# LED_SEQUENCER.net
KiCad netlist of a schematic drawn in Altium Designer
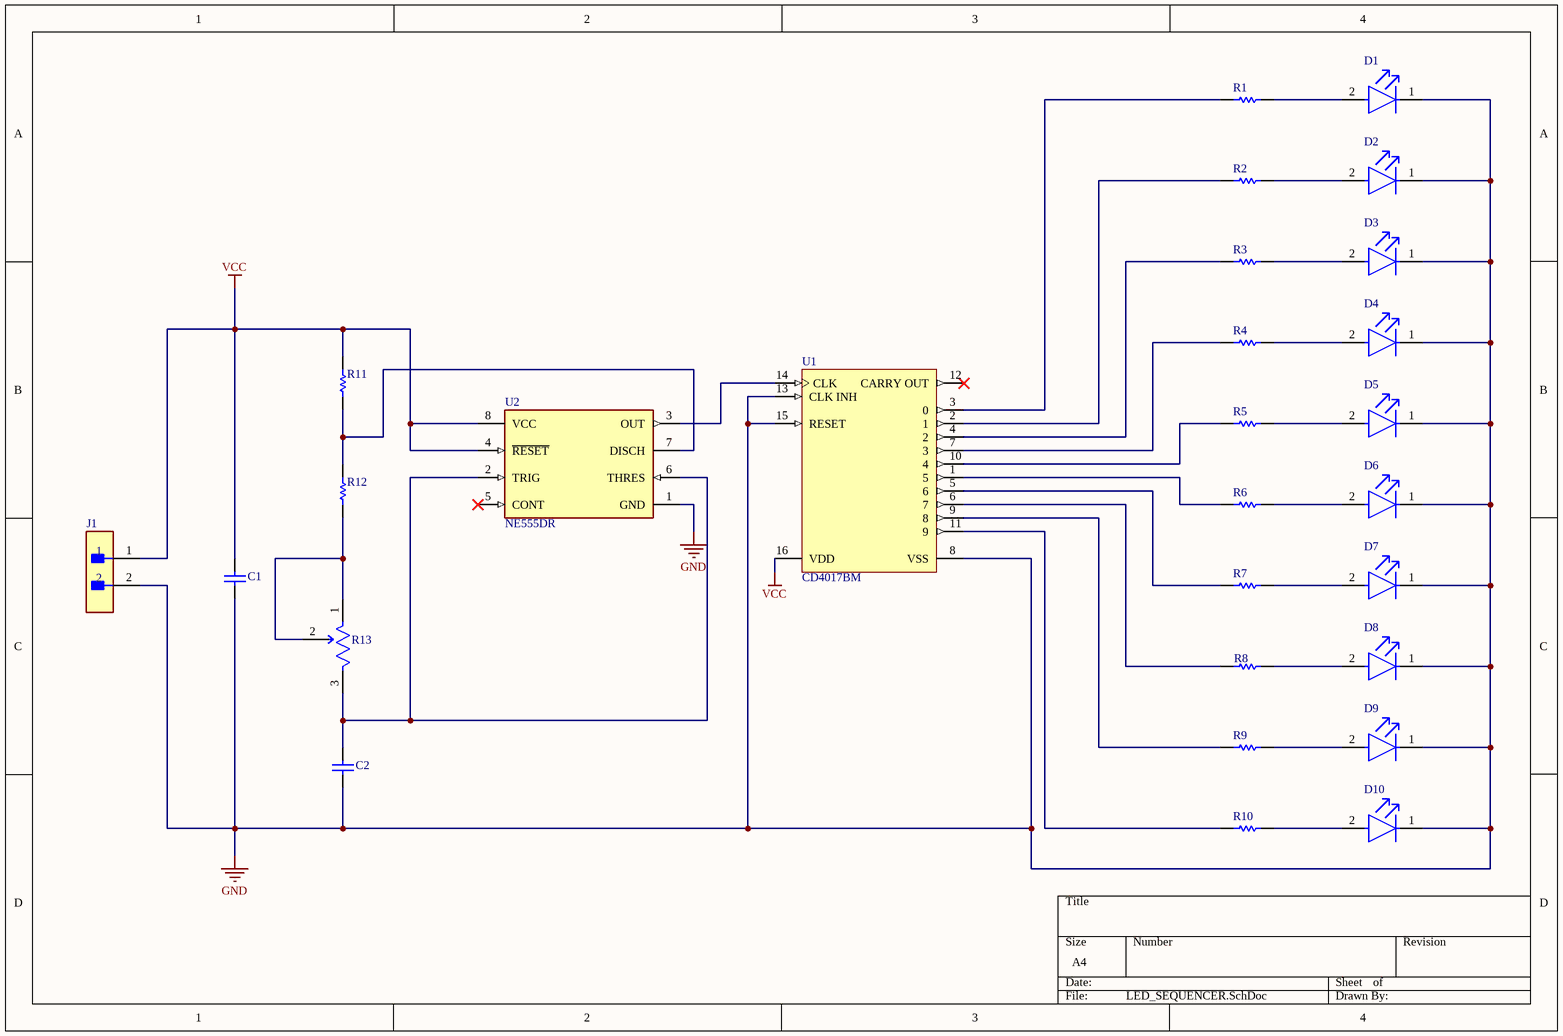
[diagram p0: LED_SEQUENCER.SchDoc]

(export (version "E")
  (design (tool "Eeschema 10.0.6"))
  (components
    (comp (ref "C1")
      (value "GRM21BR71H105KA12L")
      (footprint "CAPC2013X135X45LL10T25")
      (fields (field (name "MANUFACTURER") "Murata"))
      (libsource (lib "Altium Content Vault") (part "CAP"))
    )
    (comp (ref "C2")
      (value "GRM21BR71H105KA12L")
      (footprint "CAPC2013X135X45LL10T25")
      (fields (field (name "MANUFACTURER") "Murata"))
      (libsource (lib "Altium Content Vault") (part "CAP"))
    )
    (comp (ref "D1")
      (value "HLMP-1301")
      (footprint "FP-HLMP-1301-MFG")
      (description "LED RED DIFFUSED T-1 T/H")
      (fields
        (field (name "OCTOPART") "https://octopart.com/hlmp-1301-broadcom-71130345")
        (field (name "MANUFACTURER") "Broadcom")
      )
      (libsource (lib "Altium Content Vault") (part "8706943c75ba83719d021d2fdc84c58"))
    )
    (comp (ref "D2")
      (value "HLMP-1301")
      (footprint "FP-HLMP-1301-MFG")
      (description "LED RED DIFFUSED T-1 T/H")
      (fields
        (field (name "OCTOPART") "https://octopart.com/hlmp-1301-broadcom-71130345")
        (field (name "MANUFACTURER") "Broadcom")
      )
      (libsource (lib "Altium Content Vault") (part "8706943c75ba83719d021d2fdc84c58"))
    )
    (comp (ref "D3")
      (value "HLMP-1301")
      (footprint "FP-HLMP-1301-MFG")
      (description "LED RED DIFFUSED T-1 T/H")
      (fields
        (field (name "OCTOPART") "https://octopart.com/hlmp-1301-broadcom-71130345")
        (field (name "MANUFACTURER") "Broadcom")
      )
      (libsource (lib "Altium Content Vault") (part "8706943c75ba83719d021d2fdc84c58"))
    )
    (comp (ref "D4")
      (value "HLMP-1301")
      (footprint "FP-HLMP-1301-MFG")
      (description "LED RED DIFFUSED T-1 T/H")
      (fields
        (field (name "OCTOPART") "https://octopart.com/hlmp-1301-broadcom-71130345")
        (field (name "MANUFACTURER") "Broadcom")
      )
      (libsource (lib "Altium Content Vault") (part "8706943c75ba83719d021d2fdc84c58"))
    )
    (comp (ref "D5")
      (value "HLMP-1301")
      (footprint "FP-HLMP-1301-MFG")
      (description "LED RED DIFFUSED T-1 T/H")
      (fields
        (field (name "OCTOPART") "https://octopart.com/hlmp-1301-broadcom-71130345")
        (field (name "MANUFACTURER") "Broadcom")
      )
      (libsource (lib "Altium Content Vault") (part "8706943c75ba83719d021d2fdc84c58"))
    )
    (comp (ref "D6")
      (value "HLMP-1301")
      (footprint "FP-HLMP-1301-MFG")
      (description "LED RED DIFFUSED T-1 T/H")
      (fields
        (field (name "OCTOPART") "https://octopart.com/hlmp-1301-broadcom-71130345")
        (field (name "MANUFACTURER") "Broadcom")
      )
      (libsource (lib "Altium Content Vault") (part "8706943c75ba83719d021d2fdc84c58"))
    )
    (comp (ref "D7")
      (value "HLMP-1301")
      (footprint "FP-HLMP-1301-MFG")
      (description "LED RED DIFFUSED T-1 T/H")
      (fields
        (field (name "OCTOPART") "https://octopart.com/hlmp-1301-broadcom-71130345")
        (field (name "MANUFACTURER") "Broadcom")
      )
      (libsource (lib "Altium Content Vault") (part "8706943c75ba83719d021d2fdc84c58"))
    )
    (comp (ref "D8")
      (value "HLMP-1301")
      (footprint "FP-HLMP-1301-MFG")
      (description "LED RED DIFFUSED T-1 T/H")
      (fields
        (field (name "OCTOPART") "https://octopart.com/hlmp-1301-broadcom-71130345")
        (field (name "MANUFACTURER") "Broadcom")
      )
      (libsource (lib "Altium Content Vault") (part "8706943c75ba83719d021d2fdc84c58"))
    )
    (comp (ref "D9")
      (value "HLMP-1301")
      (footprint "FP-HLMP-1301-MFG")
      (description "LED RED DIFFUSED T-1 T/H")
      (fields
        (field (name "OCTOPART") "https://octopart.com/hlmp-1301-broadcom-71130345")
        (field (name "MANUFACTURER") "Broadcom")
      )
      (libsource (lib "Altium Content Vault") (part "8706943c75ba83719d021d2fdc84c58"))
    )
    (comp (ref "D10")
      (value "HLMP-1301")
      (footprint "FP-HLMP-1301-MFG")
      (description "LED RED DIFFUSED T-1 T/H")
      (fields
        (field (name "OCTOPART") "https://octopart.com/hlmp-1301-broadcom-71130345")
        (field (name "MANUFACTURER") "Broadcom")
      )
      (libsource (lib "Altium Content Vault") (part "8706943c75ba83719d021d2fdc84c58"))
    )
    (comp (ref "J1")
      (value "M20-9990246")
      (footprint "FP-M20-9990246-MFG")
      (description "Connector Header Through Hole 2 position 0.100\" (2.54mm)")
      (fields (field (name "OCTOPART") "https://octopart.com/m20-9990246-harwin-2590635"))
      (libsource (lib "Altium Content Vault") (part "3bc925449376181038e59eaffc5286c"))
    )
    (comp (ref "R1")
      (value "RC0805FR-071KL")
      (footprint "RESC2013X60X35ML10T20")
      (description "Chip Resistor, 1 KOhm, +/- 1%, 125 mW, -55 to 155 degC, 0805 (2012 Metric), RoHS, Tape and Reel")
      (fields (field (name "TOLERANCE") "1%") (field (name "MANUFACTURER") "Yageo"))
      (libsource (lib "Altium Content Vault") (part "RES-2"))
    )
    (comp (ref "R2")
      (value "RC0805FR-071KL")
      (footprint "RESC2013X60X35ML10T20")
      (description "Chip Resistor, 1 KOhm, +/- 1%, 125 mW, -55 to 155 degC, 0805 (2012 Metric), RoHS, Tape and Reel")
      (fields (field (name "TOLERANCE") "1%") (field (name "MANUFACTURER") "Yageo"))
      (libsource (lib "Altium Content Vault") (part "RES-2"))
    )
    (comp (ref "R3")
      (value "RC0805FR-071KL")
      (footprint "RESC2013X60X35ML10T20")
      (description "Chip Resistor, 1 KOhm, +/- 1%, 125 mW, -55 to 155 degC, 0805 (2012 Metric), RoHS, Tape and Reel")
      (fields (field (name "TOLERANCE") "1%") (field (name "MANUFACTURER") "Yageo"))
      (libsource (lib "Altium Content Vault") (part "RES-2"))
    )
    (comp (ref "R4")
      (value "RC0805FR-071KL")
      (footprint "RESC2013X60X35ML10T20")
      (description "Chip Resistor, 1 KOhm, +/- 1%, 125 mW, -55 to 155 degC, 0805 (2012 Metric), RoHS, Tape and Reel")
      (fields (field (name "TOLERANCE") "1%") (field (name "MANUFACTURER") "Yageo"))
      (libsource (lib "Altium Content Vault") (part "RES-2"))
    )
    (comp (ref "R5")
      (value "RC0805FR-071KL")
      (footprint "RESC2013X60X35ML10T20")
      (description "Chip Resistor, 1 KOhm, +/- 1%, 125 mW, -55 to 155 degC, 0805 (2012 Metric), RoHS, Tape and Reel")
      (fields (field (name "TOLERANCE") "1%") (field (name "MANUFACTURER") "Yageo"))
      (libsource (lib "Altium Content Vault") (part "RES-2"))
    )
    (comp (ref "R6")
      (value "RC0805FR-071KL")
      (footprint "RESC2013X60X35ML10T20")
      (description "Chip Resistor, 1 KOhm, +/- 1%, 125 mW, -55 to 155 degC, 0805 (2012 Metric), RoHS, Tape and Reel")
      (fields (field (name "TOLERANCE") "1%") (field (name "MANUFACTURER") "Yageo"))
      (libsource (lib "Altium Content Vault") (part "RES-2"))
    )
    (comp (ref "R7")
      (value "RC0805FR-071KL")
      (footprint "RESC2013X60X35ML10T20")
      (description "Chip Resistor, 1 KOhm, +/- 1%, 125 mW, -55 to 155 degC, 0805 (2012 Metric), RoHS, Tape and Reel")
      (fields (field (name "TOLERANCE") "1%") (field (name "MANUFACTURER") "Yageo"))
      (libsource (lib "Altium Content Vault") (part "RES-2"))
    )
    (comp (ref "R8")
      (value "RC0805FR-071KL")
      (footprint "RESC2013X60X35ML10T20")
      (description "Chip Resistor, 1 KOhm, +/- 1%, 125 mW, -55 to 155 degC, 0805 (2012 Metric), RoHS, Tape and Reel")
      (fields (field (name "TOLERANCE") "1%") (field (name "MANUFACTURER") "Yageo"))
      (libsource (lib "Altium Content Vault") (part "RES-2"))
    )
    (comp (ref "R9")
      (value "RC0805FR-071KL")
      (footprint "RESC2013X60X35ML10T20")
      (description "Chip Resistor, 1 KOhm, +/- 1%, 125 mW, -55 to 155 degC, 0805 (2012 Metric), RoHS, Tape and Reel")
      (fields (field (name "TOLERANCE") "1%") (field (name "MANUFACTURER") "Yageo"))
      (libsource (lib "Altium Content Vault") (part "RES-2"))
    )
    (comp (ref "R10")
      (value "RC0805FR-071KL")
      (footprint "RESC2013X60X35ML10T20")
      (description "Chip Resistor, 1 KOhm, +/- 1%, 125 mW, -55 to 155 degC, 0805 (2012 Metric), RoHS, Tape and Reel")
      (fields (field (name "TOLERANCE") "1%") (field (name "MANUFACTURER") "Yageo"))
      (libsource (lib "Altium Content Vault") (part "RES-2"))
    )
    (comp (ref "R11")
      (value "RC0805FR-071KL")
      (footprint "RESC2013X60X35ML10T20")
      (description "Chip Resistor, 1 KOhm, +/- 1%, 125 mW, -55 to 155 degC, 0805 (2012 Metric), RoHS, Tape and Reel")
      (fields (field (name "TOLERANCE") "1%") (field (name "MANUFACTURER") "Yageo"))
      (libsource (lib "Altium Content Vault") (part "RES-2"))
    )
    (comp (ref "R12")
      (value "RC0805FR-071KL")
      (footprint "RESC2013X60X35ML10T20")
      (description "Chip Resistor, 1 KOhm, +/- 1%, 125 mW, -55 to 155 degC, 0805 (2012 Metric), RoHS, Tape and Reel")
      (fields (field (name "TOLERANCE") "1%") (field (name "MANUFACTURER") "Yageo"))
      (libsource (lib "Altium Content Vault") (part "RES-2"))
    )
    (comp (ref "R13")
      (value "3386P-1-104LF")
      (footprint "FP-3386P-MFG")
      (description "TRIMMER 100K OHM 0.5W PC PIN TOP")
      (fields (field (name "TOLERANCE") "10%"))
      (libsource (lib "Altium Content Vault") (part "13357d81287629c2fd191d242cfa50c"))
    )
    (comp (ref "U1")
      (value "CD4017BM")
      (footprint "D0016A_N")
      (description "CMOS Decade Counter with 10 Decoded Outputs, D0016A, TUBE")
      (fields
        (field (name "GENERIC PART NUMBER") "CD4017B")
        (field (name "MANUFACTURER") "Texas Instruments")
      )
      (libsource (lib "Altium Content Vault") (part "TI-CD4017B-16"))
    )
    (comp (ref "U2")
      (value "NE555DR")
      (footprint "FP-D0008A-IPC_A")
      (description "IC OSC SGL TIMER 100KHZ 8-SOIC")
      (libsource (lib "Altium Content Vault") (part "a29bba90211dec1890110b94dad7d53"))
    )
  )
  (nets
    (net (code "1") (name "GND") (class "Default")
      (node (ref "C1") (pin "1") (pinfunction "1_1") (pintype "passive"))
      (node (ref "C2") (pin "1") (pinfunction "1_1") (pintype "passive"))
      (node (ref "D1") (pin "1") (pinfunction "C_1") (pintype "passive"))
      (node (ref "D10") (pin "1") (pinfunction "C_1") (pintype "passive"))
      (node (ref "D2") (pin "1") (pinfunction "C_1") (pintype "passive"))
      (node (ref "D3") (pin "1") (pinfunction "C_1") (pintype "passive"))
      (node (ref "D4") (pin "1") (pinfunction "C_1") (pintype "passive"))
      (node (ref "D5") (pin "1") (pinfunction "C_1") (pintype "passive"))
      (node (ref "D6") (pin "1") (pinfunction "C_1") (pintype "passive"))
      (node (ref "D7") (pin "1") (pinfunction "C_1") (pintype "passive"))
      (node (ref "D8") (pin "1") (pinfunction "C_1") (pintype "passive"))
      (node (ref "D9") (pin "1") (pinfunction "C_1") (pintype "passive"))
      (node (ref "J1") (pin "2") (pinfunction "2_2") (pintype "passive"))
      (node (ref "U1") (pin "13") (pinfunction "CLK_INH_13") (pintype "input"))
      (node (ref "U1") (pin "15") (pinfunction "RESET_15") (pintype "input"))
      (node (ref "U1") (pin "8") (pinfunction "VSS_8") (pintype "power_in"))
      (node (ref "U2") (pin "1") (pinfunction "GND_1") (pintype "power_in"))
    )
    (net (code "2") (name "Net-(D1-A)") (class "Default")
      (node (ref "D1") (pin "2") (pinfunction "A_2") (pintype "passive"))
      (node (ref "R1") (pin "2") (pinfunction "2_2") (pintype "passive"))
    )
    (net (code "3") (name "Net-(D2-A)") (class "Default")
      (node (ref "D2") (pin "2") (pinfunction "A_2") (pintype "passive"))
      (node (ref "R2") (pin "2") (pinfunction "2_2") (pintype "passive"))
    )
    (net (code "4") (name "Net-(D3-A)") (class "Default")
      (node (ref "D3") (pin "2") (pinfunction "A_2") (pintype "passive"))
      (node (ref "R3") (pin "2") (pinfunction "2_2") (pintype "passive"))
    )
    (net (code "5") (name "Net-(D4-A)") (class "Default")
      (node (ref "D4") (pin "2") (pinfunction "A_2") (pintype "passive"))
      (node (ref "R4") (pin "2") (pinfunction "2_2") (pintype "passive"))
    )
    (net (code "6") (name "Net-(D5-A)") (class "Default")
      (node (ref "D5") (pin "2") (pinfunction "A_2") (pintype "passive"))
      (node (ref "R5") (pin "2") (pinfunction "2_2") (pintype "passive"))
    )
    (net (code "7") (name "Net-(D6-A)") (class "Default")
      (node (ref "D6") (pin "2") (pinfunction "A_2") (pintype "passive"))
      (node (ref "R6") (pin "2") (pinfunction "2_2") (pintype "passive"))
    )
    (net (code "8") (name "Net-(D7-A)") (class "Default")
      (node (ref "D7") (pin "2") (pinfunction "A_2") (pintype "passive"))
      (node (ref "R7") (pin "2") (pinfunction "2_2") (pintype "passive"))
    )
    (net (code "9") (name "Net-(D8-A)") (class "Default")
      (node (ref "D8") (pin "2") (pinfunction "A_2") (pintype "passive"))
      (node (ref "R8") (pin "2") (pinfunction "2_2") (pintype "passive"))
    )
    (net (code "10") (name "Net-(D9-A)") (class "Default")
      (node (ref "D9") (pin "2") (pinfunction "A_2") (pintype "passive"))
      (node (ref "R9") (pin "2") (pinfunction "2_2") (pintype "passive"))
    )
    (net (code "11") (name "Net-(D10-A)") (class "Default")
      (node (ref "D10") (pin "2") (pinfunction "A_2") (pintype "passive"))
      (node (ref "R10") (pin "2") (pinfunction "2_2") (pintype "passive"))
    )
    (net (code "12") (name "Net-(R13-CCW)") (class "Default")
      (node (ref "R12") (pin "1") (pinfunction "1_1") (pintype "passive"))
      (node (ref "R13") (pin "1") (pinfunction "CCW_1") (pintype "passive"))
      (node (ref "R13") (pin "2") (pinfunction "WIPER_2") (pintype "passive"))
    )
    (net (code "13") (name "Net-(R13-CW)") (class "Default")
      (node (ref "C2") (pin "2") (pinfunction "2_2") (pintype "passive"))
      (node (ref "R13") (pin "3") (pinfunction "CW_3") (pintype "passive"))
      (node (ref "U2") (pin "2") (pinfunction "TRIG_2") (pintype "input"))
      (node (ref "U2") (pin "6") (pinfunction "THRES_6") (pintype "input"))
    )
    (net (code "14") (name "Net-(U1-0)") (class "Default")
      (node (ref "R1") (pin "1") (pinfunction "1_1") (pintype "passive"))
      (node (ref "U1") (pin "3") (pinfunction "0_3") (pintype "output"))
    )
    (net (code "15") (name "Net-(U1-1)") (class "Default")
      (node (ref "R2") (pin "1") (pinfunction "1_1") (pintype "passive"))
      (node (ref "U1") (pin "2") (pinfunction "1_2") (pintype "output"))
    )
    (net (code "16") (name "Net-(U1-2)") (class "Default")
      (node (ref "R3") (pin "1") (pinfunction "1_1") (pintype "passive"))
      (node (ref "U1") (pin "4") (pinfunction "2_4") (pintype "output"))
    )
    (net (code "17") (name "Net-(U1-3)") (class "Default")
      (node (ref "R4") (pin "1") (pinfunction "1_1") (pintype "passive"))
      (node (ref "U1") (pin "7") (pinfunction "3_7") (pintype "output"))
    )
    (net (code "18") (name "Net-(U1-4)") (class "Default")
      (node (ref "R5") (pin "1") (pinfunction "1_1") (pintype "passive"))
      (node (ref "U1") (pin "10") (pinfunction "4_10") (pintype "output"))
    )
    (net (code "19") (name "Net-(U1-5)") (class "Default")
      (node (ref "R6") (pin "1") (pinfunction "1_1") (pintype "passive"))
      (node (ref "U1") (pin "1") (pinfunction "5_1") (pintype "output"))
    )
    (net (code "20") (name "Net-(U1-6)") (class "Default")
      (node (ref "R7") (pin "1") (pinfunction "1_1") (pintype "passive"))
      (node (ref "U1") (pin "5") (pinfunction "6_5") (pintype "output"))
    )
    (net (code "21") (name "Net-(U1-7)") (class "Default")
      (node (ref "R8") (pin "1") (pinfunction "1_1") (pintype "passive"))
      (node (ref "U1") (pin "6") (pinfunction "7_6") (pintype "output"))
    )
    (net (code "22") (name "Net-(U1-8)") (class "Default")
      (node (ref "R9") (pin "1") (pinfunction "1_1") (pintype "passive"))
      (node (ref "U1") (pin "9") (pinfunction "8_9") (pintype "output"))
    )
    (net (code "23") (name "Net-(U1-9)") (class "Default")
      (node (ref "R10") (pin "1") (pinfunction "1_1") (pintype "passive"))
      (node (ref "U1") (pin "11") (pinfunction "9_11") (pintype "output"))
    )
    (net (code "24") (name "Net-(U1-CLK)") (class "Default")
      (node (ref "U1") (pin "14") (pinfunction "CLK_14") (pintype "input"))
      (node (ref "U2") (pin "3") (pinfunction "OUT_3") (pintype "output"))
    )
    (net (code "25") (name "Net-(U2-DISCH)") (class "Default")
      (node (ref "R11") (pin "1") (pinfunction "1_1") (pintype "passive"))
      (node (ref "R12") (pin "2") (pinfunction "2_2") (pintype "passive"))
      (node (ref "U2") (pin "7") (pinfunction "DISCH_7") (pintype "open_collector"))
    )
    (net (code "26") (name "VCC") (class "Default")
      (node (ref "C1") (pin "2") (pinfunction "2_2") (pintype "passive"))
      (node (ref "J1") (pin "1") (pinfunction "1_1") (pintype "passive"))
      (node (ref "R11") (pin "2") (pinfunction "2_2") (pintype "passive"))
      (node (ref "U1") (pin "16") (pinfunction "VDD_16") (pintype "power_in"))
      (node (ref "U2") (pin "4") (pinfunction "~{RESET}_4") (pintype "input"))
      (node (ref "U2") (pin "8") (pinfunction "VCC_8") (pintype "power_in"))
    )
    (net (code "27") (name "unconnected-(U1-CARRY_OUT-Pad12)") (class "Default")
      (node (ref "U1") (pin "12") (pinfunction "CARRY_OUT_12") (pintype "output+no_connect"))
    )
    (net (code "28") (name "unconnected-(U2-CONT-Pad5)") (class "Default")
      (node (ref "U2") (pin "5") (pinfunction "CONT_5") (pintype "input+no_connect"))
    )
  )
)
